# panatap.net
KiCad netlist of a schematic drawn in EAGLE
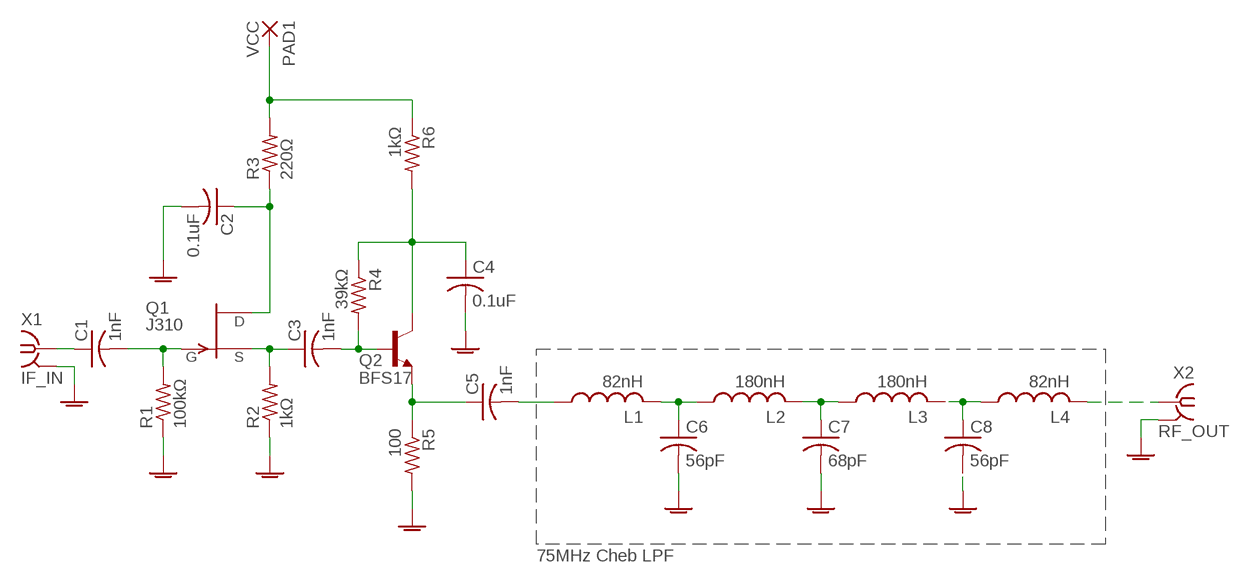
[diagram p0: schematic, sheet 1]

(export (version "E")
  (design (tool "Eeschema 10.0.6"))
  (components
    (comp (ref "C1")
      (value "1nF")
      (footprint "eagle-import:C1206")
      (libsource (lib "eagle-import") (part "C-USC1206"))
    )
    (comp (ref "C2")
      (value "0.1uF")
      (footprint "eagle-import:C1206")
      (libsource (lib "eagle-import") (part "C-USC1206"))
    )
    (comp (ref "C3")
      (value "1nF")
      (footprint "eagle-import:C1206")
      (libsource (lib "eagle-import") (part "C-USC1206"))
    )
    (comp (ref "C4")
      (value "0.1uF")
      (footprint "eagle-import:C1206")
      (libsource (lib "eagle-import") (part "C-USC1206"))
    )
    (comp (ref "C5")
      (value "1nF")
      (footprint "eagle-import:C1206")
      (libsource (lib "eagle-import") (part "C-USC1206"))
    )
    (comp (ref "C6")
      (value "56pF")
      (footprint "eagle-import:C1206")
      (libsource (lib "eagle-import") (part "C-USC1206"))
    )
    (comp (ref "C7")
      (value "68pF")
      (footprint "eagle-import:C1206")
      (libsource (lib "eagle-import") (part "C-USC1206"))
    )
    (comp (ref "C8")
      (value "56pF")
      (footprint "eagle-import:C1206")
      (libsource (lib "eagle-import") (part "C-USC1206"))
    )
    (comp (ref "L1")
      (value "82nH")
      (footprint "eagle-import:L2012C")
      (libsource (lib "eagle-import") (part "L-USL2012C"))
    )
    (comp (ref "L2")
      (value "180nH")
      (footprint "eagle-import:L2012C")
      (libsource (lib "eagle-import") (part "L-USL2012C"))
    )
    (comp (ref "L3")
      (value "180nH")
      (footprint "eagle-import:L2012C")
      (libsource (lib "eagle-import") (part "L-USL2012C"))
    )
    (comp (ref "L4")
      (value "82nH")
      (footprint "eagle-import:L2012C")
      (libsource (lib "eagle-import") (part "L-USL2012C"))
    )
    (comp (ref "PAD1")
      (value "VCC")
      (footprint "eagle-import:SMD2,54-5,08")
      (libsource (lib "eagle-import") (part "WIREPADSMD2,54-5,08"))
    )
    (comp (ref "Q1")
      (value "J310")
      (footprint "eagle-import:SOT23")
      (libsource (lib "eagle-import") (part "?20SST1"))
    )
    (comp (ref "Q2")
      (value "BFS17")
      (footprint "eagle-import:SOT23")
      (libsource (lib "eagle-import") (part "BC846"))
    )
    (comp (ref "R1")
      (value "100kΩ")
      (footprint "eagle-import:R1206")
      (libsource (lib "eagle-import") (part "R-US_R1206"))
    )
    (comp (ref "R2")
      (value "1kΩ")
      (footprint "eagle-import:R1206")
      (libsource (lib "eagle-import") (part "R-US_R1206"))
    )
    (comp (ref "R3")
      (value "220Ω")
      (footprint "eagle-import:R1206")
      (libsource (lib "eagle-import") (part "R-US_R1206"))
    )
    (comp (ref "R4")
      (value "39kΩ")
      (footprint "eagle-import:R1206")
      (libsource (lib "eagle-import") (part "R-US_R1206"))
    )
    (comp (ref "R5")
      (value "100")
      (footprint "eagle-import:R1206")
      (libsource (lib "eagle-import") (part "R-US_R1206"))
    )
    (comp (ref "R6")
      (value "1kΩ")
      (footprint "eagle-import:R1206")
      (libsource (lib "eagle-import") (part "R-US_R1206"))
    )
    (comp (ref "X1")
      (value "IF_IN")
      (footprint "eagle-import:J502-ND-142-0701-801_806")
      (fields (field (name "MF") "JOHNSON COMPONENTS") (field (name "MPN") "142-0701-801"))
      (libsource (lib "eagle-import") (part "SMA-142-0701-801/806"))
    )
    (comp (ref "X2")
      (value "RF_OUT")
      (footprint "eagle-import:J502-ND-142-0701-801_806")
      (fields (field (name "MF") "JOHNSON COMPONENTS") (field (name "MPN") "142-0701-801"))
      (libsource (lib "eagle-import") (part "SMA-142-0701-801/806"))
    )
  )
  (nets
    (net (code "1") (name "GNDA") (class "Default")
      (node (ref "C2") (pin "2") (pinfunction "2_2") (pintype "passive"))
      (node (ref "C4") (pin "2") (pinfunction "2_2") (pintype "passive"))
      (node (ref "C6") (pin "2") (pinfunction "2_2") (pintype "passive"))
      (node (ref "C7") (pin "2") (pinfunction "2_2") (pintype "passive"))
      (node (ref "C8") (pin "2") (pinfunction "2_2") (pintype "passive"))
      (node (ref "R1") (pin "1") (pinfunction "1_1") (pintype "passive"))
      (node (ref "R2") (pin "1") (pinfunction "1_1") (pintype "passive"))
      (node (ref "R5") (pin "2") (pinfunction "2_2") (pintype "passive"))
      (node (ref "X1") (pin "G@1") (pinfunction "2_G@1") (pintype "passive"))
      (node (ref "X1") (pin "G@2") (pinfunction "2_G@2") (pintype "passive"))
      (node (ref "X1") (pin "G@3") (pinfunction "2_G@3") (pintype "passive"))
      (node (ref "X1") (pin "G@4") (pinfunction "2_G@4") (pintype "passive"))
      (node (ref "X2") (pin "G@1") (pinfunction "2_G@1") (pintype "passive"))
      (node (ref "X2") (pin "G@2") (pinfunction "2_G@2") (pintype "passive"))
      (node (ref "X2") (pin "G@3") (pinfunction "2_G@3") (pintype "passive"))
      (node (ref "X2") (pin "G@4") (pinfunction "2_G@4") (pintype "passive"))
    )
    (net (code "2") (name "Net-(C1-Pad1)") (class "Default")
      (node (ref "C1") (pin "1") (pinfunction "1_1") (pintype "passive"))
      (node (ref "X1") (pin "1") (pinfunction "1_1") (pintype "passive"))
    )
    (net (code "3") (name "Net-(C5-Pad2)") (class "Default")
      (node (ref "C5") (pin "2") (pinfunction "2_2") (pintype "passive"))
      (node (ref "L1") (pin "1") (pinfunction "1_1") (pintype "passive"))
    )
    (net (code "4") (name "Net-(C6-Pad1)") (class "Default")
      (node (ref "C6") (pin "1") (pinfunction "1_1") (pintype "passive"))
      (node (ref "L1") (pin "2") (pinfunction "2_2") (pintype "passive"))
      (node (ref "L2") (pin "1") (pinfunction "1_1") (pintype "passive"))
    )
    (net (code "5") (name "Net-(C7-Pad1)") (class "Default")
      (node (ref "C7") (pin "1") (pinfunction "1_1") (pintype "passive"))
      (node (ref "L2") (pin "2") (pinfunction "2_2") (pintype "passive"))
      (node (ref "L3") (pin "1") (pinfunction "1_1") (pintype "passive"))
    )
    (net (code "6") (name "Net-(C8-Pad1)") (class "Default")
      (node (ref "C8") (pin "1") (pinfunction "1_1") (pintype "passive"))
      (node (ref "L3") (pin "2") (pinfunction "2_2") (pintype "passive"))
      (node (ref "L4") (pin "1") (pinfunction "1_1") (pintype "passive"))
    )
    (net (code "7") (name "Net-(L4-Pad2)") (class "Default")
      (node (ref "L4") (pin "2") (pinfunction "2_2") (pintype "passive"))
      (node (ref "X2") (pin "1") (pinfunction "1_1") (pintype "passive"))
    )
    (net (code "8") (name "Net-(PAD1-P)") (class "Default")
      (node (ref "PAD1") (pin "1") (pinfunction "P_1") (pintype "passive"))
      (node (ref "R3") (pin "2") (pinfunction "2_2") (pintype "passive"))
      (node (ref "R6") (pin "1") (pinfunction "1_1") (pintype "passive"))
    )
    (net (code "9") (name "Net-(Q1-D)") (class "Default")
      (node (ref "C2") (pin "1") (pinfunction "1_1") (pintype "passive"))
      (node (ref "Q1") (pin "1") (pinfunction "D_1") (pintype "passive"))
      (node (ref "R3") (pin "1") (pinfunction "1_1") (pintype "passive"))
    )
    (net (code "10") (name "Net-(Q1-G)") (class "Default")
      (node (ref "C1") (pin "2") (pinfunction "2_2") (pintype "passive"))
      (node (ref "Q1") (pin "3") (pinfunction "G_3") (pintype "passive"))
      (node (ref "R1") (pin "2") (pinfunction "2_2") (pintype "passive"))
    )
    (net (code "11") (name "Net-(Q1-S)") (class "Default")
      (node (ref "C3") (pin "1") (pinfunction "1_1") (pintype "passive"))
      (node (ref "Q1") (pin "2") (pinfunction "S_2") (pintype "passive"))
      (node (ref "R2") (pin "2") (pinfunction "2_2") (pintype "passive"))
    )
    (net (code "12") (name "Net-(Q2-B)") (class "Default")
      (node (ref "C3") (pin "2") (pinfunction "2_2") (pintype "passive"))
      (node (ref "Q2") (pin "1") (pinfunction "B_1") (pintype "passive"))
      (node (ref "R4") (pin "2") (pinfunction "2_2") (pintype "passive"))
    )
    (net (code "13") (name "Net-(Q2-C)") (class "Default")
      (node (ref "C4") (pin "1") (pinfunction "1_1") (pintype "passive"))
      (node (ref "Q2") (pin "3") (pinfunction "C_3") (pintype "passive"))
      (node (ref "R4") (pin "1") (pinfunction "1_1") (pintype "passive"))
      (node (ref "R6") (pin "2") (pinfunction "2_2") (pintype "passive"))
    )
    (net (code "14") (name "Net-(Q2-E)") (class "Default")
      (node (ref "C5") (pin "1") (pinfunction "1_1") (pintype "passive"))
      (node (ref "Q2") (pin "2") (pinfunction "E_2") (pintype "passive"))
      (node (ref "R5") (pin "1") (pinfunction "1_1") (pintype "passive"))
    )
  )
)
